# Digital.net
KiCad netlist of a schematic drawn in Altium Designer
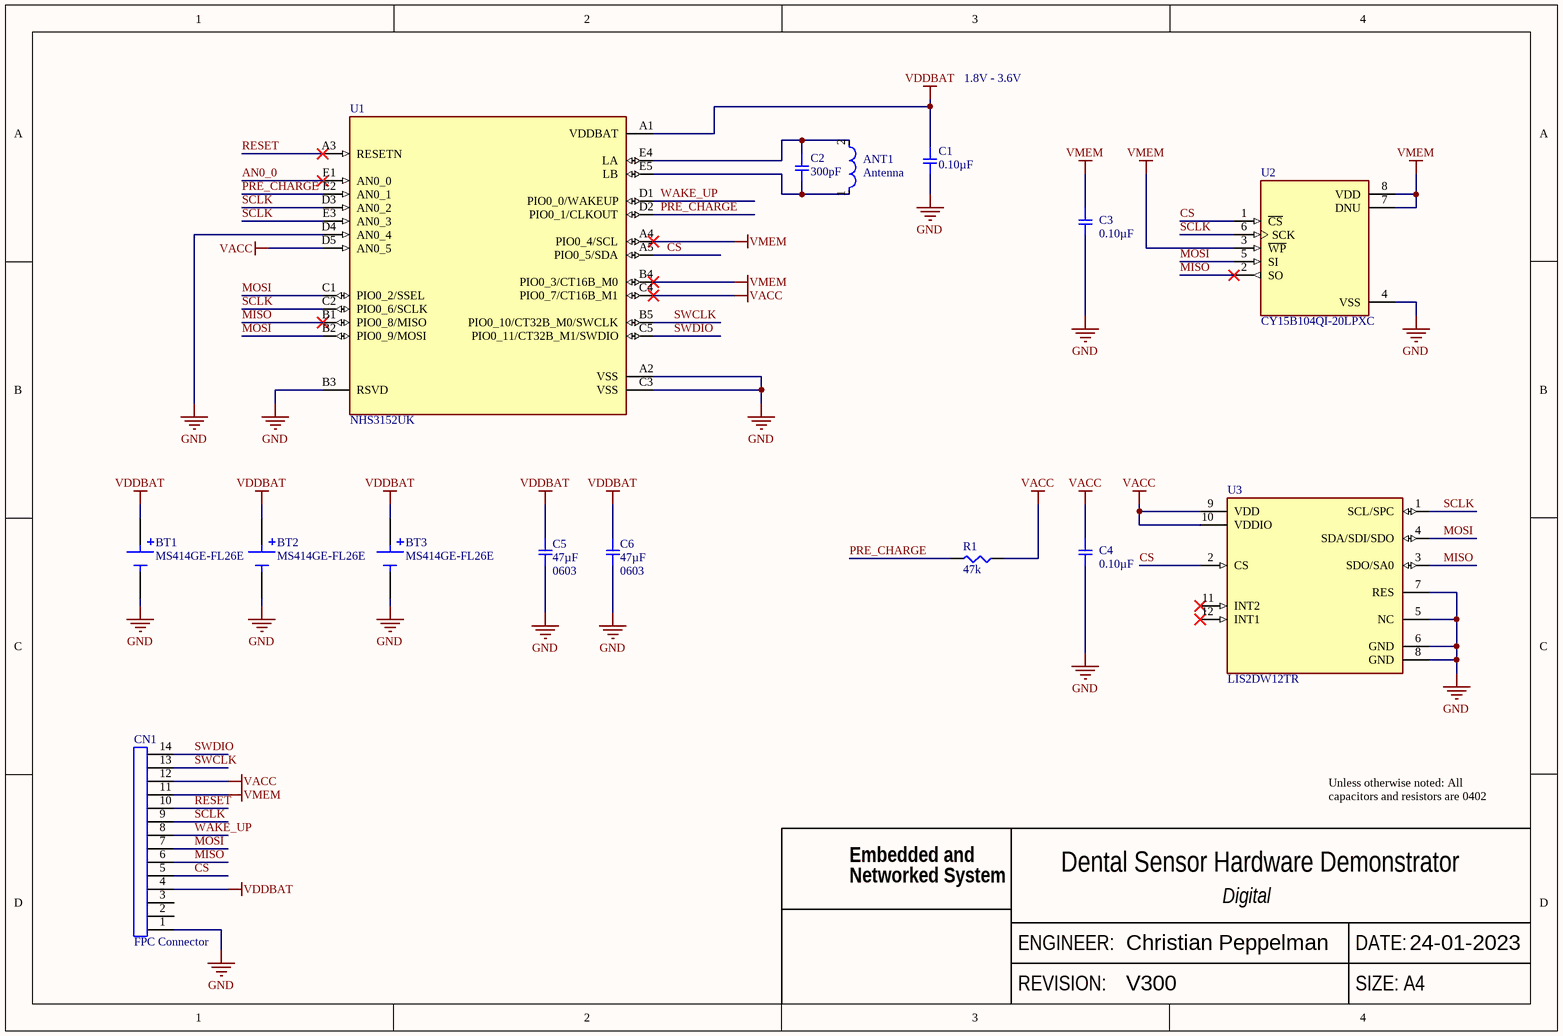
[diagram p0: Digital.SchDoc]

(export (version "E")
  (design (tool "Eeschema 10.0.6"))
  (components
    (comp (ref "ANT1")
      (value "Antenna")
      (footprint "NFC Antenna")
      (description "Track 0.2; Gap 0.1; Height 4.6; Width 14.5;")
      (libsource (lib "Library") (part "NFC Antenna"))
    )
    (comp (ref "BT1")
      (value "MS414GE-FL26E")
      (footprint "MS414GE-FL26E")
      (description "Coin, 4.8mm 3V Lithium Battery Rechargeable (Secondary) 2mAh")
      (fields (field (name "MF") "Seiko"))
      (libsource (lib "Library") (part "MS414GE-FL26E"))
    )
    (comp (ref "BT2")
      (value "MS414GE-FL26E")
      (footprint "MS414GE-FL26E")
      (description "Coin, 4.8mm 3V Lithium Battery Rechargeable (Secondary) 2mAh")
      (fields (field (name "MF") "Seiko"))
      (libsource (lib "Library") (part "MS414GE-FL26E"))
    )
    (comp (ref "BT3")
      (value "MS414GE-FL26E")
      (footprint "MS414GE-FL26E")
      (description "Coin, 4.8mm 3V Lithium Battery Rechargeable (Secondary) 2mAh")
      (fields (field (name "MF") "Seiko"))
      (libsource (lib "Library") (part "MS414GE-FL26E"))
    )
    (comp (ref "C1")
      (value "0.10µF")
      (footprint "RESC1005X03N")
      (description "CAP CER 0.1UF 6.3V X5R 0402")
      (fields
        (field (name "DIGI-KEY PART NUMBER") "490-6287-1-ND")
        (field (name "PART NUMBER") "GRM155R60J104KA01D")
      )
      (libsource (lib "capacitor_murata_0402") (part "GRM155R60J104KA01D"))
    )
    (comp (ref "C2")
      (value "300pF")
      (footprint "RESC1005X03N")
      (description "CAP CER 300PF 50V NP0 0402")
      (fields
        (field (name "DIGI-KEY PART NUMBER") "490-3234-1-ND")
        (field (name "PART NUMBER") "GRM1555C1H301JA01D")
      )
      (libsource (lib "capacitor_murata_0402") (part "GRM1555C1H301JA01D"))
    )
    (comp (ref "C3")
      (value "0.10µF")
      (footprint "RESC1005X03N")
      (description "CAP CER 0.1UF 6.3V X5R 0402")
      (fields
        (field (name "DIGI-KEY PART NUMBER") "490-6287-1-ND")
        (field (name "PART NUMBER") "GRM155R60J104KA01D")
      )
      (libsource (lib "capacitor_murata_0402") (part "GRM155R60J104KA01D"))
    )
    (comp (ref "C4")
      (value "0.10µF")
      (footprint "RESC1005X03N")
      (description "CAP CER 0.1UF 6.3V X5R 0402")
      (fields
        (field (name "DIGI-KEY PART NUMBER") "490-6287-1-ND")
        (field (name "PART NUMBER") "GRM155R60J104KA01D")
      )
      (libsource (lib "capacitor_murata_0402") (part "GRM155R60J104KA01D"))
    )
    (comp (ref "C5")
      (value "47µF")
      (footprint "CAPC1608X12N")
      (description "CAP CER 47UF 6.3V X5R 0603")
      (fields
        (field (name "DIGI-KEY PART NUMBER") "490-13211-1-ND")
        (field (name "PART NUMBER") "GRJ155R60J106ME11D")
        (field (name "PACKAGE / CASE") "0603")
      )
      (libsource (lib "capacitor_murata_0402") (part "GRJ155R60J106ME11D"))
    )
    (comp (ref "C6")
      (value "47µF")
      (footprint "CAPC1608X12N")
      (description "CAP CER 47UF 6.3V X5R 0603")
      (fields
        (field (name "DIGI-KEY PART NUMBER") "490-13211-1-ND")
        (field (name "PART NUMBER") "GRJ155R60J106ME11D")
        (field (name "PACKAGE / CASE") "0603")
      )
      (libsource (lib "capacitor_murata_0402") (part "GRJ155R60J106ME11D"))
    )
    (comp (ref "CN1")
      (value "FPC Connector")
      (footprint "52745-1497")
      (description "FFC / FPC Board Connector, 0.5 mm, 14 Contacts, Receptacle, Easy-On 52745, Surface Mount, Top")
      (libsource (lib "Library") (part "52745-1497"))
    )
    (comp (ref "R1")
      (value "47k")
      (footprint "CAPC1005X03N")
      (description "RES SMD 47K OHM 1% 1/10W 0402")
      (fields
        (field (name "PART NUMBER") "ERJ-2RKF4702X")
        (field (name "DIGI-KEY PART NUMBER") "P47.0KLCT-ND")
      )
      (libsource (lib "Panasonic_ERJ_0402") (part "ERJ-2RKF4702X"))
    )
    (comp (ref "U1")
      (value "NHS3152UK")
      (footprint "WLCSP25")
      (description "ARM-microcontrollers - MCU NTAG NHS3152 NFC")
      (libsource (lib "Library") (part "NHS3152UK"))
    )
    (comp (ref "U2")
      (value "CY15B104QI-20LPXC")
      (footprint "8-GQFN")
      (description "FRAM (Ferroelectric RAM) Memory IC 4Mbit SPI 20 MHz 8-GQFN (3.23x3.28)")
      (libsource (lib "Library") (part "CY15B104QI-20LPXC"))
    )
    (comp (ref "U3")
      (value "LIS2DW12TR")
      (footprint "FP-LGA12-DM00170568-MFG")
      (description "ACCEL 2-16G I2C/SPI 12LGA")
      (fields
        (field (name "OCTOPART") "https://octopart.com/lis2dw12tr-stmicroelectronics-77080925")
        (field (name "MANUFACTURER") "STMicroelectronics")
      )
      (libsource (lib "Altium Content Vault") (part "8197bdef8f004bf043f7592a5d62978"))
    )
  )
  (nets
    (net (code "1") (name "/AN0_0") (class "Default")
      (node (ref "U1") (pin "E1") (pinfunction "AN0_0_E1") (pintype "input+no_connect"))
    )
    (net (code "2") (name "/CS") (class "Default")
      (node (ref "CN1") (pin "5") (pintype "passive"))
      (node (ref "U1") (pin "A5") (pinfunction "PIO0_5/SDA_A5") (pintype "bidirectional"))
      (node (ref "U2") (pin "1") (pinfunction "~{CS}_1") (pintype "input"))
      (node (ref "U3") (pin "2") (pinfunction "CS_2") (pintype "input"))
    )
    (net (code "3") (name "/MISO") (class "Default")
      (node (ref "CN1") (pin "6") (pintype "passive"))
      (node (ref "U1") (pin "B1") (pinfunction "PIO0_8/MISO_B1") (pintype "bidirectional"))
      (node (ref "U2") (pin "2") (pinfunction "SO_2") (pintype "output"))
      (node (ref "U3") (pin "3") (pinfunction "SDO/SA0_3") (pintype "bidirectional"))
    )
    (net (code "4") (name "/MOSI") (class "Default")
      (node (ref "CN1") (pin "7") (pintype "passive"))
      (node (ref "U1") (pin "B2") (pinfunction "PIO0_9/MOSI_B2") (pintype "bidirectional"))
      (node (ref "U1") (pin "C1") (pinfunction "PIO0_2/SSEL_C1") (pintype "bidirectional"))
      (node (ref "U2") (pin "5") (pinfunction "SI_5") (pintype "input"))
      (node (ref "U3") (pin "4") (pinfunction "SDA/SDI/SDO_4") (pintype "bidirectional"))
    )
    (net (code "5") (name "/PRE_CHARGE") (class "Default")
      (node (ref "R1") (pin "2") (pinfunction "2_2") (pintype "passive"))
      (node (ref "U1") (pin "D2") (pinfunction "PIO0_1/CLKOUT_D2") (pintype "bidirectional"))
      (node (ref "U1") (pin "E2") (pinfunction "AN0_1_E2") (pintype "input"))
    )
    (net (code "6") (name "/RESET") (class "Default")
      (node (ref "CN1") (pin "10") (pintype "passive"))
      (node (ref "U1") (pin "A3") (pinfunction "RESETN_A3") (pintype "input"))
    )
    (net (code "7") (name "/SCLK") (class "Default")
      (node (ref "CN1") (pin "9") (pintype "passive"))
      (node (ref "U1") (pin "C2") (pinfunction "PIO0_6/SCLK_C2") (pintype "bidirectional"))
      (node (ref "U1") (pin "D3") (pinfunction "AN0_2_D3") (pintype "input"))
      (node (ref "U1") (pin "E3") (pinfunction "AN0_3_E3") (pintype "input"))
      (node (ref "U2") (pin "6") (pinfunction "SCK_6") (pintype "input"))
      (node (ref "U3") (pin "1") (pinfunction "SCL/SPC_1") (pintype "bidirectional"))
    )
    (net (code "8") (name "/SWCLK") (class "Default")
      (node (ref "CN1") (pin "13") (pintype "passive"))
      (node (ref "U1") (pin "B5") (pinfunction "PIO0_10/CT32B_M0/SWCLK_B5") (pintype "bidirectional"))
    )
    (net (code "9") (name "/SWDIO") (class "Default")
      (node (ref "CN1") (pin "14") (pintype "passive"))
      (node (ref "U1") (pin "C5") (pinfunction "PIO0_11/CT32B_M1/SWDIO_C5") (pintype "bidirectional"))
    )
    (net (code "10") (name "/WAKE_UP") (class "Default")
      (node (ref "CN1") (pin "8") (pintype "passive"))
      (node (ref "U1") (pin "D1") (pinfunction "PIO0_0/WAKEUP_D1") (pintype "bidirectional"))
    )
    (net (code "11") (name "GND") (class "Default")
      (node (ref "BT1") (pin "NEG") (pinfunction "NEG_NEG") (pintype "passive"))
      (node (ref "BT2") (pin "NEG") (pinfunction "NEG_NEG") (pintype "passive"))
      (node (ref "BT3") (pin "NEG") (pinfunction "NEG_NEG") (pintype "passive"))
      (node (ref "C1") (pin "2") (pinfunction "2_2") (pintype "passive"))
      (node (ref "C3") (pin "2") (pinfunction "2_2") (pintype "passive"))
      (node (ref "C4") (pin "2") (pinfunction "2_2") (pintype "passive"))
      (node (ref "C5") (pin "2") (pinfunction "2_2") (pintype "passive"))
      (node (ref "C6") (pin "2") (pinfunction "2_2") (pintype "passive"))
      (node (ref "CN1") (pin "1") (pintype "passive"))
      (node (ref "U1") (pin "A2") (pinfunction "VSS_A2") (pintype "power_in"))
      (node (ref "U1") (pin "B3") (pinfunction "RSVD_B3") (pintype "passive"))
      (node (ref "U1") (pin "C3") (pinfunction "VSS_C3") (pintype "power_in"))
      (node (ref "U1") (pin "D4") (pinfunction "AN0_4_D4") (pintype "input"))
      (node (ref "U2") (pin "4") (pinfunction "VSS_4") (pintype "power_in"))
      (node (ref "U3") (pin "5") (pinfunction "NC_5") (pintype "passive"))
      (node (ref "U3") (pin "6") (pinfunction "GND_6") (pintype "power_in"))
      (node (ref "U3") (pin "7") (pinfunction "RES_7") (pintype "passive"))
      (node (ref "U3") (pin "8") (pinfunction "GND_8") (pintype "power_in"))
    )
    (net (code "12") (name "Net-(U1-LA)") (class "Default")
      (node (ref "ANT1") (pin "2") (pinfunction "2_2") (pintype "passive"))
      (node (ref "C2") (pin "1") (pinfunction "1_1") (pintype "passive"))
      (node (ref "U1") (pin "E4") (pinfunction "LA_E4") (pintype "bidirectional"))
    )
    (net (code "13") (name "Net-(U1-LB)") (class "Default")
      (node (ref "ANT1") (pin "1") (pinfunction "1_1") (pintype "passive"))
      (node (ref "C2") (pin "2") (pinfunction "2_2") (pintype "passive"))
      (node (ref "U1") (pin "E5") (pinfunction "LB_E5") (pintype "bidirectional"))
    )
    (net (code "14") (name "VACC") (class "Default")
      (node (ref "C4") (pin "1") (pinfunction "1_1") (pintype "passive"))
      (node (ref "CN1") (pin "12") (pintype "passive"))
      (node (ref "R1") (pin "1") (pinfunction "1_1") (pintype "passive"))
      (node (ref "U1") (pin "C4") (pinfunction "PIO0_7/CT16B_M1_C4") (pintype "bidirectional"))
      (node (ref "U1") (pin "D5") (pinfunction "AN0_5_D5") (pintype "input"))
      (node (ref "U3") (pin "10") (pinfunction "VDDIO_10") (pintype "power_in"))
      (node (ref "U3") (pin "9") (pinfunction "VDD_9") (pintype "power_in"))
    )
    (net (code "15") (name "VDDBAT") (class "Default")
      (node (ref "BT1") (pin "POS") (pinfunction "POS_POS") (pintype "passive"))
      (node (ref "BT2") (pin "POS") (pinfunction "POS_POS") (pintype "passive"))
      (node (ref "BT3") (pin "POS") (pinfunction "POS_POS") (pintype "passive"))
      (node (ref "C1") (pin "1") (pinfunction "1_1") (pintype "passive"))
      (node (ref "C5") (pin "1") (pinfunction "1_1") (pintype "passive"))
      (node (ref "C6") (pin "1") (pinfunction "1_1") (pintype "passive"))
      (node (ref "CN1") (pin "4") (pintype "passive"))
      (node (ref "U1") (pin "A1") (pinfunction "VDDBAT_A1") (pintype "power_in"))
    )
    (net (code "16") (name "VMEM") (class "Default")
      (node (ref "C3") (pin "1") (pinfunction "1_1") (pintype "passive"))
      (node (ref "CN1") (pin "11") (pintype "passive"))
      (node (ref "U1") (pin "A4") (pinfunction "PIO0_4/SCL_A4") (pintype "bidirectional"))
      (node (ref "U1") (pin "B4") (pinfunction "PIO0_3/CT16B_M0_B4") (pintype "bidirectional"))
      (node (ref "U2") (pin "3") (pinfunction "~{WP}_3") (pintype "input"))
      (node (ref "U2") (pin "7") (pinfunction "DNU_7") (pintype "passive"))
      (node (ref "U2") (pin "8") (pinfunction "VDD_8") (pintype "power_in"))
    )
    (net (code "17") (name "unconnected-(CN1-Pad2)") (class "Default")
      (node (ref "CN1") (pin "2") (pintype "passive"))
    )
    (net (code "18") (name "unconnected-(CN1-Pad3)") (class "Default")
      (node (ref "CN1") (pin "3") (pintype "passive"))
    )
    (net (code "19") (name "unconnected-(U3-INT1-Pad12)") (class "Default")
      (node (ref "U3") (pin "12") (pinfunction "INT1_12") (pintype "input+no_connect"))
    )
    (net (code "20") (name "unconnected-(U3-INT2-Pad11)") (class "Default")
      (node (ref "U3") (pin "11") (pinfunction "INT2_11") (pintype "input+no_connect"))
    )
  )
)
